# NESpi.net
KiCad netlist of a schematic drawn in EAGLE
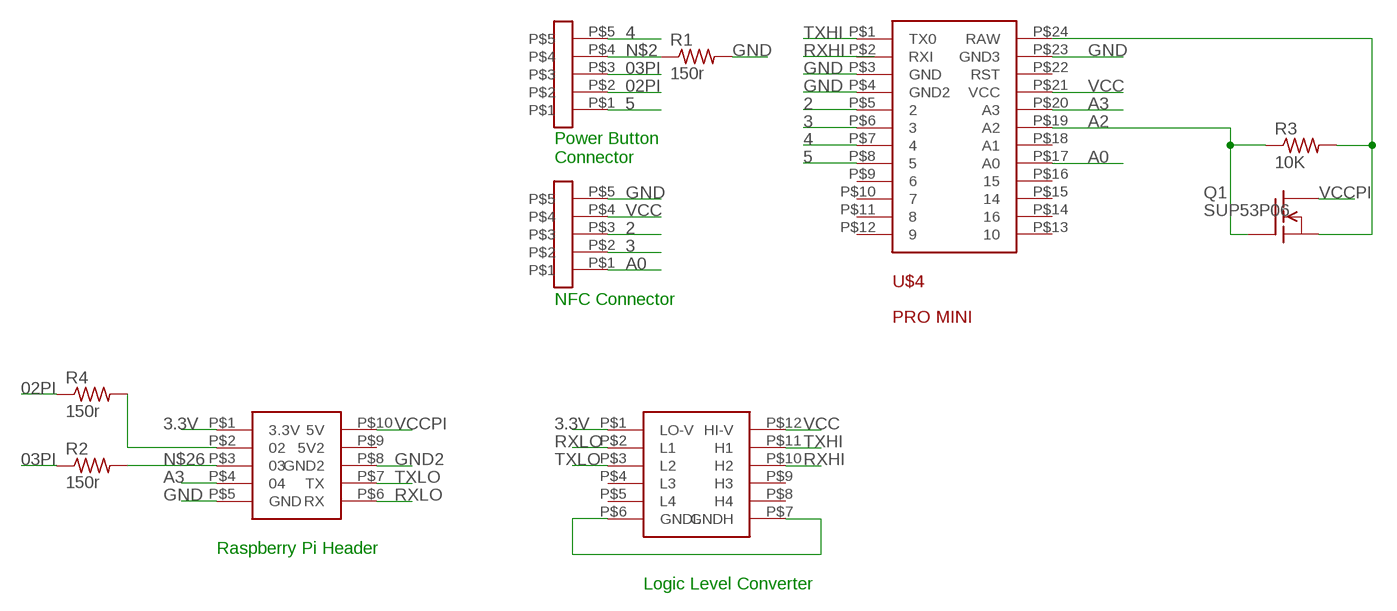
[diagram p0: schematic, sheet 1]

(export (version "E")
  (design (tool "Eeschema 10.0.6"))
  (components
    (comp (ref "Q1")
      (value "SUP53P06")
      (footprint "eagle-import:TO220")
      (libsource (lib "eagle-import") (part "IRF620"))
    )
    (comp (ref "R1")
      (value "150r")
      (footprint "eagle-import:VMTA55")
      (libsource (lib "eagle-import") (part "R-US_VMTA55"))
    )
    (comp (ref "R2")
      (value "150r")
      (footprint "eagle-import:VMTA55")
      (libsource (lib "eagle-import") (part "R-US_VMTA55"))
    )
    (comp (ref "R3")
      (value "10K")
      (footprint "eagle-import:VMTA55")
      (libsource (lib "eagle-import") (part "R-US_VMTA55"))
    )
    (comp (ref "R4")
      (value "150r")
      (footprint "eagle-import:VMTA55")
      (libsource (lib "eagle-import") (part "R-US_VMTA55"))
    )
    (comp (ref "U$1")
      (value "DIP5")
      (footprint "eagle-import:DIP5")
      (libsource (lib "eagle-import") (part "DIP5"))
    )
    (comp (ref "U$3")
      (value "DIP10")
      (footprint "eagle-import:DIP10")
      (libsource (lib "eagle-import") (part "DIP10"))
    )
    (comp (ref "U$4")
      (value "PROMICRODIP24")
      (footprint "eagle-import:DIP24")
      (libsource (lib "eagle-import") (part "PROMICRODIP24"))
    )
    (comp (ref "U$5")
      (value "LEV_CONVERTER")
      (footprint "eagle-import:LEV_CONVERTER")
      (libsource (lib "eagle-import") (part "LEV_CONVERTER"))
    )
    (comp (ref "U$6")
      (value "DIP5")
      (footprint "eagle-import:DIP5")
      (libsource (lib "eagle-import") (part "DIP5"))
    )
  )
  (nets
    (net (code "1") (name "/2") (class "Default")
      (node (ref "U$4") (pin "P$5") (pinfunction "2_P$5") (pintype "bidirectional"))
      (node (ref "U$6") (pin "P$3") (pinfunction "P$3_P$3") (pintype "bidirectional"))
    )
    (net (code "2") (name "/02PI") (class "Default")
      (node (ref "R4") (pin "1") (pinfunction "1_1") (pintype "passive"))
      (node (ref "U$1") (pin "P$2") (pinfunction "P$2_P$2") (pintype "bidirectional"))
    )
    (net (code "3") (name "/3") (class "Default")
      (node (ref "U$4") (pin "P$6") (pinfunction "3_P$6") (pintype "bidirectional"))
      (node (ref "U$6") (pin "P$2") (pinfunction "P$2_P$2") (pintype "bidirectional"))
    )
    (net (code "4") (name "/3.3V") (class "Default")
      (node (ref "U$3") (pin "P$1") (pinfunction "3.3V_P$1") (pintype "bidirectional"))
      (node (ref "U$5") (pin "P$1") (pinfunction "LO-V_P$1") (pintype "bidirectional"))
    )
    (net (code "5") (name "/03PI") (class "Default")
      (node (ref "R2") (pin "1") (pinfunction "1_1") (pintype "passive"))
      (node (ref "U$1") (pin "P$3") (pinfunction "P$3_P$3") (pintype "bidirectional"))
    )
    (net (code "6") (name "/4") (class "Default")
      (node (ref "U$1") (pin "P$5") (pinfunction "P$5_P$5") (pintype "bidirectional"))
      (node (ref "U$4") (pin "P$7") (pinfunction "4_P$7") (pintype "bidirectional"))
    )
    (net (code "7") (name "/5") (class "Default")
      (node (ref "U$1") (pin "P$1") (pinfunction "P$1_P$1") (pintype "bidirectional"))
      (node (ref "U$4") (pin "P$8") (pinfunction "5_P$8") (pintype "bidirectional"))
    )
    (net (code "8") (name "/A0") (class "Default")
      (node (ref "U$4") (pin "P$17") (pinfunction "A0_P$17") (pintype "bidirectional"))
      (node (ref "U$6") (pin "P$1") (pinfunction "P$1_P$1") (pintype "bidirectional"))
    )
    (net (code "9") (name "/A2") (class "Default")
      (node (ref "Q1") (pin "1") (pinfunction "G_1") (pintype "passive"))
      (node (ref "R3") (pin "1") (pinfunction "1_1") (pintype "passive"))
      (node (ref "U$4") (pin "P$19") (pinfunction "A2_P$19") (pintype "bidirectional"))
    )
    (net (code "10") (name "/A3") (class "Default")
      (node (ref "U$3") (pin "P$4") (pinfunction "04_P$4") (pintype "bidirectional"))
      (node (ref "U$4") (pin "P$20") (pinfunction "A3_P$20") (pintype "bidirectional"))
    )
    (net (code "11") (name "/GND") (class "Default")
      (node (ref "R1") (pin "2") (pinfunction "2_2") (pintype "passive"))
      (node (ref "U$3") (pin "P$5") (pinfunction "GND_P$5") (pintype "bidirectional"))
      (node (ref "U$4") (pin "P$23") (pinfunction "GND3_P$23") (pintype "bidirectional"))
      (node (ref "U$4") (pin "P$3") (pinfunction "GND_P$3") (pintype "bidirectional"))
      (node (ref "U$4") (pin "P$4") (pinfunction "GND2_P$4") (pintype "bidirectional"))
      (node (ref "U$5") (pin "P$6") (pinfunction "GNDL_P$6") (pintype "bidirectional"))
      (node (ref "U$5") (pin "P$7") (pinfunction "GNDH_P$7") (pintype "bidirectional"))
      (node (ref "U$6") (pin "P$5") (pinfunction "P$5_P$5") (pintype "bidirectional"))
    )
    (net (code "12") (name "/GND2") (class "Default")
      (node (ref "U$3") (pin "P$8") (pinfunction "GND2_P$8") (pintype "bidirectional"))
    )
    (net (code "13") (name "/N$2") (class "Default")
      (node (ref "R1") (pin "1") (pinfunction "1_1") (pintype "passive"))
      (node (ref "U$1") (pin "P$4") (pinfunction "P$4_P$4") (pintype "bidirectional"))
    )
    (net (code "14") (name "/N$26") (class "Default")
      (node (ref "R2") (pin "2") (pinfunction "2_2") (pintype "passive"))
      (node (ref "U$3") (pin "P$3") (pinfunction "03_P$3") (pintype "bidirectional"))
    )
    (net (code "15") (name "/RXHI") (class "Default")
      (node (ref "U$5") (pin "P$10") (pinfunction "H2_P$10") (pintype "bidirectional"))
    )
    (net (code "16") (name "/RXLO") (class "Default")
      (node (ref "U$3") (pin "P$6") (pinfunction "RX_P$6") (pintype "bidirectional"))
      (node (ref "U$5") (pin "P$2") (pinfunction "L1_P$2") (pintype "bidirectional"))
    )
    (net (code "17") (name "/TXHI") (class "Default")
      (node (ref "U$4") (pin "P$1") (pinfunction "TX0_P$1") (pintype "bidirectional"))
      (node (ref "U$5") (pin "P$11") (pinfunction "H1_P$11") (pintype "bidirectional"))
    )
    (net (code "18") (name "/TXLO") (class "Default")
      (node (ref "U$3") (pin "P$7") (pinfunction "TX_P$7") (pintype "bidirectional"))
      (node (ref "U$5") (pin "P$3") (pinfunction "L2_P$3") (pintype "bidirectional"))
    )
    (net (code "19") (name "/VCC") (class "Default")
      (node (ref "U$4") (pin "P$21") (pinfunction "VCC_P$21") (pintype "bidirectional"))
      (node (ref "U$5") (pin "P$12") (pinfunction "HI-V_P$12") (pintype "bidirectional"))
      (node (ref "U$6") (pin "P$4") (pinfunction "P$4_P$4") (pintype "bidirectional"))
    )
    (net (code "20") (name "/VCCPI") (class "Default")
      (node (ref "Q1") (pin "2") (pinfunction "D_2") (pintype "passive"))
      (node (ref "U$3") (pin "P$10") (pinfunction "5V_P$10") (pintype "bidirectional"))
    )
    (net (code "21") (name "Net-(Q1-S)") (class "Default")
      (node (ref "Q1") (pin "3") (pinfunction "S_3") (pintype "passive"))
      (node (ref "R3") (pin "2") (pinfunction "2_2") (pintype "passive"))
      (node (ref "U$4") (pin "P$24") (pinfunction "RAW_P$24") (pintype "bidirectional"))
    )
    (net (code "22") (name "Net-(U$3-02)") (class "Default")
      (node (ref "R4") (pin "2") (pinfunction "2_2") (pintype "passive"))
      (node (ref "U$3") (pin "P$2") (pinfunction "02_P$2") (pintype "bidirectional"))
    )
    (net (code "23") (name "unconnected-(U$3-5V2-PadP$9)") (class "Default")
      (node (ref "U$3") (pin "P$9") (pinfunction "5V2_P$9") (pintype "bidirectional"))
    )
    (net (code "24") (name "unconnected-(U$4-6-PadP$9)") (class "Default")
      (node (ref "U$4") (pin "P$9") (pinfunction "6_P$9") (pintype "bidirectional"))
    )
    (net (code "25") (name "unconnected-(U$4-7-PadP$10)") (class "Default")
      (node (ref "U$4") (pin "P$10") (pinfunction "7_P$10") (pintype "bidirectional"))
    )
    (net (code "26") (name "unconnected-(U$4-8-PadP$11)") (class "Default")
      (node (ref "U$4") (pin "P$11") (pinfunction "8_P$11") (pintype "bidirectional"))
    )
    (net (code "27") (name "unconnected-(U$4-9-PadP$12)") (class "Default")
      (node (ref "U$4") (pin "P$12") (pinfunction "9_P$12") (pintype "bidirectional"))
    )
    (net (code "28") (name "unconnected-(U$4-10-PadP$13)") (class "Default")
      (node (ref "U$4") (pin "P$13") (pinfunction "10_P$13") (pintype "bidirectional"))
    )
    (net (code "29") (name "unconnected-(U$4-14-PadP$15)") (class "Default")
      (node (ref "U$4") (pin "P$15") (pinfunction "14_P$15") (pintype "bidirectional"))
    )
    (net (code "30") (name "unconnected-(U$4-15-PadP$16)") (class "Default")
      (node (ref "U$4") (pin "P$16") (pinfunction "15_P$16") (pintype "bidirectional"))
    )
    (net (code "31") (name "unconnected-(U$4-16-PadP$14)") (class "Default")
      (node (ref "U$4") (pin "P$14") (pinfunction "16_P$14") (pintype "bidirectional"))
    )
    (net (code "32") (name "unconnected-(U$4-A1-PadP$18)") (class "Default")
      (node (ref "U$4") (pin "P$18") (pinfunction "A1_P$18") (pintype "bidirectional"))
    )
    (net (code "33") (name "unconnected-(U$4-RST-PadP$22)") (class "Default")
      (node (ref "U$4") (pin "P$22") (pinfunction "RST_P$22") (pintype "bidirectional"))
    )
    (net (code "34") (name "unconnected-(U$4-RXI-PadP$2)") (class "Default")
      (node (ref "U$4") (pin "P$2") (pinfunction "RXI_P$2") (pintype "bidirectional"))
    )
    (net (code "35") (name "unconnected-(U$5-H3-PadP$9)") (class "Default")
      (node (ref "U$5") (pin "P$9") (pinfunction "H3_P$9") (pintype "bidirectional"))
    )
    (net (code "36") (name "unconnected-(U$5-H4-PadP$8)") (class "Default")
      (node (ref "U$5") (pin "P$8") (pinfunction "H4_P$8") (pintype "bidirectional"))
    )
    (net (code "37") (name "unconnected-(U$5-L3-PadP$4)") (class "Default")
      (node (ref "U$5") (pin "P$4") (pinfunction "L3_P$4") (pintype "bidirectional"))
    )
    (net (code "38") (name "unconnected-(U$5-L4-PadP$5)") (class "Default")
      (node (ref "U$5") (pin "P$5") (pinfunction "L4_P$5") (pintype "bidirectional"))
    )
  )
)
